# uC.net
KiCad netlist of a schematic drawn in Altium Designer
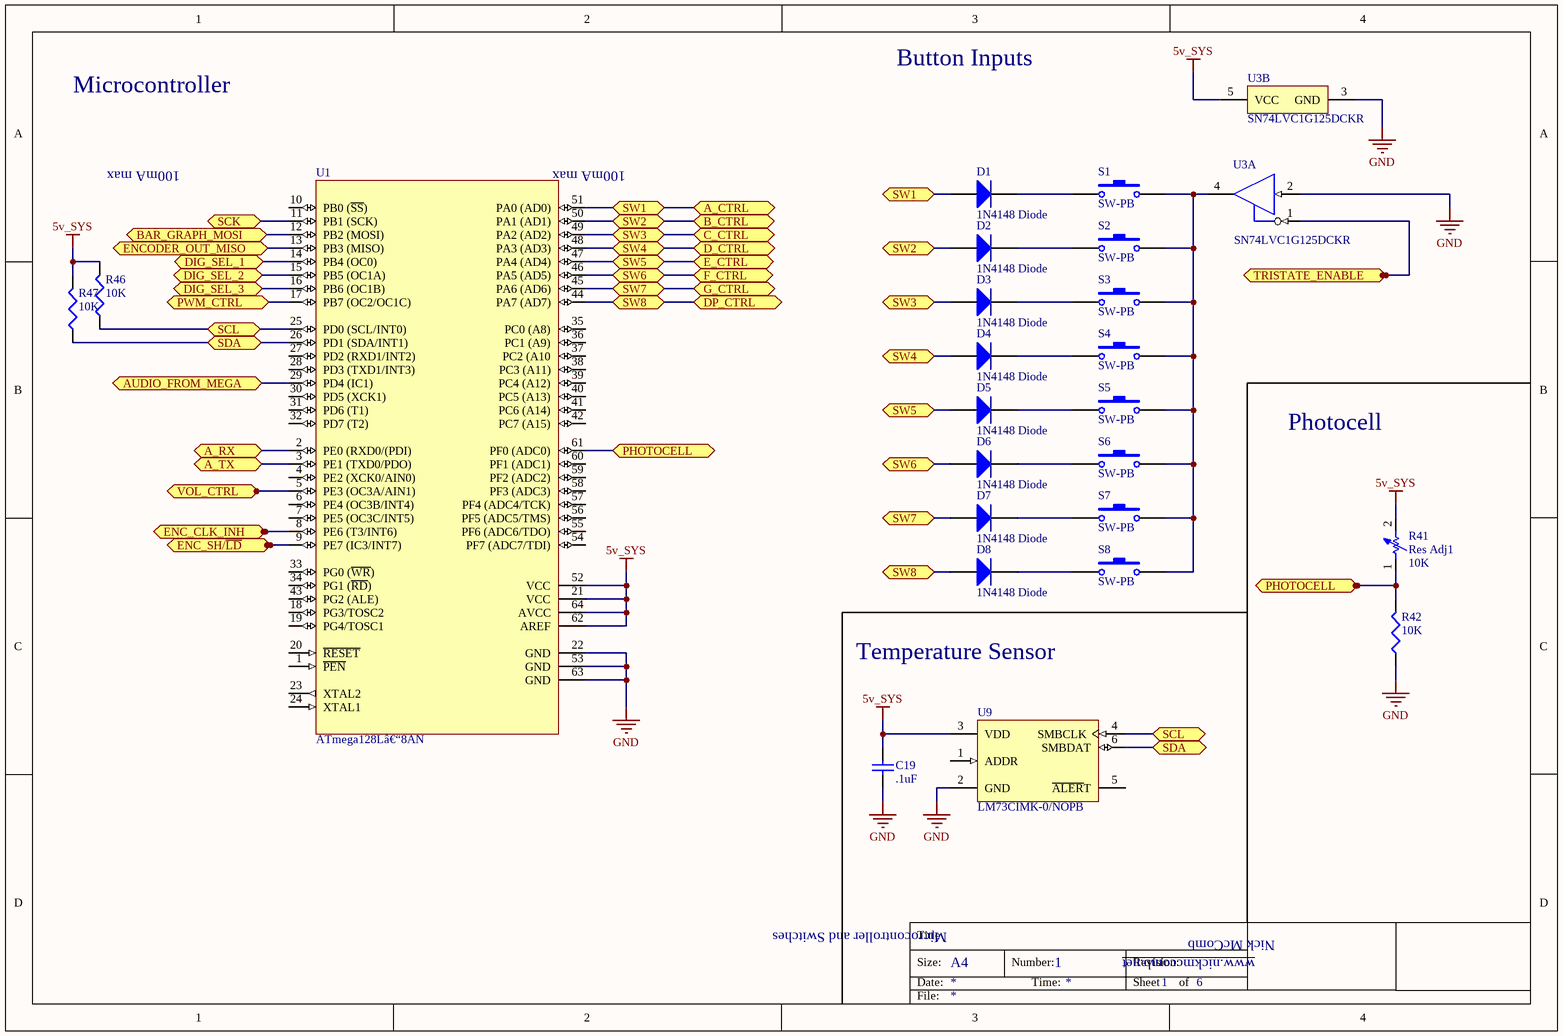
[diagram p0: uC.SchDoc]

(export (version "E")
  (design (tool "Eeschema 10.0.6"))
  (components
    (comp (ref "C19")
      (value ".1uF")
      (footprint "C0805")
      (description "Capacitor")
      (fields (field (name "Comment") "0805 style, by default") (field (name "PUBLISHER") "Altium Limited"))
      (libsource (lib "mega48") (part "Cap"))
    )
    (comp (ref "D1")
      (value "1N4148 Diode")
      (footprint "S01575 Diode")
      (description "Diode")
      (libsource (lib "lab2") (part "Diode"))
    )
    (comp (ref "D2")
      (value "1N4148 Diode")
      (footprint "S01575 Diode")
      (description "Diode")
      (libsource (lib "lab2") (part "Diode"))
    )
    (comp (ref "D3")
      (value "1N4148 Diode")
      (footprint "S01575 Diode")
      (description "Diode")
      (libsource (lib "lab2") (part "Diode"))
    )
    (comp (ref "D4")
      (value "1N4148 Diode")
      (footprint "S01575 Diode")
      (description "Diode")
      (libsource (lib "lab2") (part "Diode"))
    )
    (comp (ref "D5")
      (value "1N4148 Diode")
      (footprint "S01575 Diode")
      (description "Diode")
      (libsource (lib "lab2") (part "Diode"))
    )
    (comp (ref "D6")
      (value "1N4148 Diode")
      (footprint "S01575 Diode")
      (description "Diode")
      (libsource (lib "lab2") (part "Diode"))
    )
    (comp (ref "D7")
      (value "1N4148 Diode")
      (footprint "S01575 Diode")
      (description "Diode")
      (libsource (lib "lab2") (part "Diode"))
    )
    (comp (ref "D8")
      (value "1N4148 Diode")
      (footprint "S01575 Diode")
      (description "Diode")
      (libsource (lib "lab2") (part "Diode"))
    )
    (comp (ref "R41")
      (value "Res Adj1")
      (footprint "LOG POT")
      (description "Variable Resistor")
      (fields (field (name "ALTIUM_VALUE") "10K"))
      (libsource (lib "lab2") (part "Res Adj1"))
    )
    (comp (ref "R42")
      (value "10K")
      (footprint "J1-0603")
      (description "Resistor")
      (fields (field (name "PUBLISHER") "Altium Limited"))
      (libsource (lib "lab2") (part "Res3"))
    )
    (comp (ref "R46")
      (value "10K")
      (footprint "J1-0603")
      (description "Resistor")
      (fields (field (name "PUBLISHER") "Altium Limited"))
      (libsource (lib "lab2") (part "Res3"))
    )
    (comp (ref "R47")
      (value "10K")
      (footprint "J1-0603")
      (description "Resistor")
      (fields (field (name "PUBLISHER") "Altium Limited"))
      (libsource (lib "lab2") (part "Res3"))
    )
    (comp (ref "S1")
      (value "SW-PB")
      (footprint "SW-PB")
      (description "Switch")
      (libsource (lib "lab2") (part "SW-PB"))
    )
    (comp (ref "S2")
      (value "SW-PB")
      (footprint "SW-PB")
      (description "Switch")
      (libsource (lib "lab2") (part "SW-PB"))
    )
    (comp (ref "S3")
      (value "SW-PB")
      (footprint "SW-PB")
      (description "Switch")
      (libsource (lib "lab2") (part "SW-PB"))
    )
    (comp (ref "S4")
      (value "SW-PB")
      (footprint "SW-PB")
      (description "Switch")
      (libsource (lib "lab2") (part "SW-PB"))
    )
    (comp (ref "S5")
      (value "SW-PB")
      (footprint "SW-PB")
      (description "Switch")
      (libsource (lib "lab2") (part "SW-PB"))
    )
    (comp (ref "S6")
      (value "SW-PB")
      (footprint "SW-PB")
      (description "Switch")
      (libsource (lib "lab2") (part "SW-PB"))
    )
    (comp (ref "S7")
      (value "SW-PB")
      (footprint "SW-PB")
      (description "Switch")
      (libsource (lib "lab2") (part "SW-PB"))
    )
    (comp (ref "S8")
      (value "SW-PB")
      (footprint "SW-PB")
      (description "Switch")
      (libsource (lib "lab2") (part "SW-PB"))
    )
    (comp (ref "U1")
      (value "ATmega128Lâ€“8AN")
      (footprint "64A_M")
      (libsource (lib "Altium Content Vault") (part "MC-8B-AT64-SQ64"))
    )
    (comp (ref "U3")
      (value "SN74LVC1G125DCKR")
      (footprint "DCK0005A_M")
      (description "Single Bus Buffer Gate With 3-State Outputs, DCK0005A, LARGE T&R")
      (fields
        (field (name "GENERIC PART NUMBER") "SN74LVC1G125")
        (field (name "MANUFACTURER") "Texas Instruments")
      )
      (libsource (lib "Altium Content Vault") (part "TI-SN74AXXXX1X125-5"))
    )
    (comp (ref "U9")
      (value "LM73CIMK-0/NOPB")
      (footprint "DDC0006A_M")
      (description "2.7V, 11- to 14- Bit Digital Temperature Sensor with 2-Wire Interface, 6-pin Tiny SOT23, Pb-Free")
      (fields (field (name "MANUFACTURER") "Texas Instruments"))
      (libsource (lib "Altium Content Vault") (part "SEN-TEMP-LM73CIMK-6"))
    )
  )
  (nets
    (net (code "1") (name "/AUDIO_FROM_MEGA") (class "Default")
      (node (ref "U1") (pin "29") (pinfunction "PD4_(IC1)_29") (pintype "bidirectional"))
    )
    (net (code "2") (name "/A_CTRL") (class "Default")
      (node (ref "D1") (pin "3") (pinfunction "A_3") (pintype "passive"))
      (node (ref "U1") (pin "51") (pinfunction "PA0_(AD0)_51") (pintype "bidirectional"))
    )
    (net (code "3") (name "/A_RX") (class "Default")
      (node (ref "U1") (pin "2") (pinfunction "PE0_(RXD0/(PDI)_2") (pintype "bidirectional"))
    )
    (net (code "4") (name "/A_TX") (class "Default")
      (node (ref "U1") (pin "3") (pinfunction "PE1_(TXD0/PDO)_3") (pintype "bidirectional"))
    )
    (net (code "5") (name "/BAR_GRAPH_MOSI") (class "Default")
      (node (ref "U1") (pin "12") (pinfunction "PB2_(MOSI)_12") (pintype "bidirectional"))
    )
    (net (code "6") (name "/B_CTRL") (class "Default")
      (node (ref "D2") (pin "3") (pinfunction "A_3") (pintype "passive"))
      (node (ref "U1") (pin "50") (pinfunction "PA1_(AD1)_50") (pintype "bidirectional"))
    )
    (net (code "7") (name "/C_CTRL") (class "Default")
      (node (ref "D3") (pin "3") (pinfunction "A_3") (pintype "passive"))
      (node (ref "U1") (pin "49") (pinfunction "PA2_(AD2)_49") (pintype "bidirectional"))
    )
    (net (code "8") (name "/DIG_SEL_1") (class "Default")
      (node (ref "U1") (pin "14") (pinfunction "PB4_(OC0)_14") (pintype "bidirectional"))
    )
    (net (code "9") (name "/DIG_SEL_2") (class "Default")
      (node (ref "U1") (pin "15") (pinfunction "PB5_(OC1A)_15") (pintype "bidirectional"))
    )
    (net (code "10") (name "/DIG_SEL_3") (class "Default")
      (node (ref "U1") (pin "16") (pinfunction "PB6_(OC1B)_16") (pintype "bidirectional"))
    )
    (net (code "11") (name "/DP_CTRL") (class "Default")
      (node (ref "D8") (pin "3") (pinfunction "A_3") (pintype "passive"))
      (node (ref "U1") (pin "44") (pinfunction "PA7_(AD7)_44") (pintype "bidirectional"))
    )
    (net (code "12") (name "/D_CTRL") (class "Default")
      (node (ref "D4") (pin "3") (pinfunction "A_3") (pintype "passive"))
      (node (ref "U1") (pin "48") (pinfunction "PA3_(AD3)_48") (pintype "bidirectional"))
    )
    (net (code "13") (name "/ENCODER_OUT_MISO") (class "Default")
      (node (ref "U1") (pin "13") (pinfunction "PB3_(MISO)_13") (pintype "bidirectional"))
    )
    (net (code "14") (name "/ENC_CLK_INH") (class "Default")
      (node (ref "U1") (pin "8") (pinfunction "PE6_(T3/INT6)_8") (pintype "bidirectional"))
    )
    (net (code "15") (name "/ENC_SH{slash}~{LD}") (class "Default")
      (node (ref "U1") (pin "9") (pinfunction "PE7_(IC3/INT7)_9") (pintype "bidirectional"))
    )
    (net (code "16") (name "/E_CTRL") (class "Default")
      (node (ref "D5") (pin "3") (pinfunction "A_3") (pintype "passive"))
      (node (ref "U1") (pin "47") (pinfunction "PA4_(AD4)_47") (pintype "bidirectional"))
    )
    (net (code "17") (name "/F_CTRL") (class "Default")
      (node (ref "D6") (pin "3") (pinfunction "A_3") (pintype "passive"))
      (node (ref "U1") (pin "46") (pinfunction "PA5_(AD5)_46") (pintype "bidirectional"))
    )
    (net (code "18") (name "/G_CTRL") (class "Default")
      (node (ref "D7") (pin "3") (pinfunction "A_3") (pintype "passive"))
      (node (ref "U1") (pin "45") (pinfunction "PA6_(AD6)_45") (pintype "bidirectional"))
    )
    (net (code "19") (name "/PHOTOCELL") (class "Default")
      (node (ref "R41") (pin "1") (pinfunction "1_1") (pintype "passive"))
      (node (ref "R42") (pin "2") (pinfunction "2_2") (pintype "passive"))
      (node (ref "U1") (pin "61") (pinfunction "PF0_(ADC0)_61") (pintype "bidirectional"))
    )
    (net (code "20") (name "/PWM_CTRL") (class "Default")
      (node (ref "U1") (pin "17") (pinfunction "PB7_(OC2/OC1C)_17") (pintype "bidirectional"))
    )
    (net (code "21") (name "/SCK") (class "Default")
      (node (ref "U1") (pin "11") (pinfunction "PB1_(SCK)_11") (pintype "bidirectional"))
    )
    (net (code "22") (name "/SCL") (class "Default")
      (node (ref "R46") (pin "1") (pinfunction "1_1") (pintype "passive"))
      (node (ref "U1") (pin "25") (pinfunction "PD0_(SCL/INT0)_25") (pintype "bidirectional"))
      (node (ref "U9") (pin "4") (pinfunction "SMBCLK_4") (pintype "input"))
    )
    (net (code "23") (name "/SDA") (class "Default")
      (node (ref "R47") (pin "1") (pinfunction "1_1") (pintype "passive"))
      (node (ref "U1") (pin "26") (pinfunction "PD1_(SDA/INT1)_26") (pintype "bidirectional"))
      (node (ref "U9") (pin "6") (pinfunction "SMBDAT_6") (pintype "bidirectional"))
    )
    (net (code "24") (name "/TRISTATE_ENABLE") (class "Default")
      (node (ref "U3") (pin "1") (pinfunction "~{OE}_1") (pintype "input"))
    )
    (net (code "25") (name "/VOL_CTRL") (class "Default")
      (node (ref "U1") (pin "5") (pinfunction "PE3_(OC3A/AIN1)_5") (pintype "bidirectional"))
    )
    (net (code "26") (name "5v_SYS") (class "Default")
      (node (ref "C19") (pin "2") (pinfunction "2_2") (pintype "passive"))
      (node (ref "R41") (pin "2") (pinfunction "2_2") (pintype "passive"))
      (node (ref "R46") (pin "2") (pinfunction "2_2") (pintype "passive"))
      (node (ref "R47") (pin "2") (pinfunction "2_2") (pintype "passive"))
      (node (ref "U1") (pin "21") (pinfunction "VCC_21") (pintype "power_in"))
      (node (ref "U1") (pin "52") (pinfunction "VCC_52") (pintype "power_in"))
      (node (ref "U1") (pin "62") (pinfunction "AREF_62") (pintype "passive"))
      (node (ref "U1") (pin "64") (pinfunction "AVCC_64") (pintype "power_in"))
      (node (ref "U3") (pin "5") (pinfunction "VCC_5") (pintype "power_in"))
      (node (ref "U9") (pin "3") (pinfunction "VDD_3") (pintype "power_in"))
    )
    (net (code "27") (name "GND") (class "Default")
      (node (ref "C19") (pin "1") (pinfunction "1_1") (pintype "passive"))
      (node (ref "R42") (pin "1") (pinfunction "1_1") (pintype "passive"))
      (node (ref "U1") (pin "22") (pinfunction "GND_22") (pintype "power_in"))
      (node (ref "U1") (pin "53") (pinfunction "GND_53") (pintype "power_in"))
      (node (ref "U1") (pin "63") (pinfunction "GND_63") (pintype "power_in"))
      (node (ref "U3") (pin "2") (pinfunction "A_2") (pintype "input"))
      (node (ref "U3") (pin "3") (pinfunction "GND_3") (pintype "power_in"))
      (node (ref "U9") (pin "2") (pinfunction "GND_2") (pintype "power_in"))
    )
    (net (code "28") (name "Net-(D1-K)") (class "Default")
      (node (ref "D1") (pin "1") (pinfunction "K_1") (pintype "passive"))
      (node (ref "S1") (pin "1") (pinfunction "1_1") (pintype "passive"))
    )
    (net (code "29") (name "Net-(D2-K)") (class "Default")
      (node (ref "D2") (pin "1") (pinfunction "K_1") (pintype "passive"))
      (node (ref "S2") (pin "1") (pinfunction "1_1") (pintype "passive"))
    )
    (net (code "30") (name "Net-(D3-K)") (class "Default")
      (node (ref "D3") (pin "1") (pinfunction "K_1") (pintype "passive"))
      (node (ref "S3") (pin "1") (pinfunction "1_1") (pintype "passive"))
    )
    (net (code "31") (name "Net-(D4-K)") (class "Default")
      (node (ref "D4") (pin "1") (pinfunction "K_1") (pintype "passive"))
      (node (ref "S4") (pin "1") (pinfunction "1_1") (pintype "passive"))
    )
    (net (code "32") (name "Net-(D5-K)") (class "Default")
      (node (ref "D5") (pin "1") (pinfunction "K_1") (pintype "passive"))
      (node (ref "S5") (pin "1") (pinfunction "1_1") (pintype "passive"))
    )
    (net (code "33") (name "Net-(D6-K)") (class "Default")
      (node (ref "D6") (pin "1") (pinfunction "K_1") (pintype "passive"))
      (node (ref "S6") (pin "1") (pinfunction "1_1") (pintype "passive"))
    )
    (net (code "34") (name "Net-(D7-K)") (class "Default")
      (node (ref "D7") (pin "1") (pinfunction "K_1") (pintype "passive"))
      (node (ref "S7") (pin "1") (pinfunction "1_1") (pintype "passive"))
    )
    (net (code "35") (name "Net-(D8-K)") (class "Default")
      (node (ref "D8") (pin "1") (pinfunction "K_1") (pintype "passive"))
      (node (ref "S8") (pin "1") (pinfunction "1_1") (pintype "passive"))
    )
    (net (code "36") (name "Net-(U3A-Y)") (class "Default")
      (node (ref "S1") (pin "2") (pinfunction "2_2") (pintype "passive"))
      (node (ref "S2") (pin "2") (pinfunction "2_2") (pintype "passive"))
      (node (ref "S3") (pin "2") (pinfunction "2_2") (pintype "passive"))
      (node (ref "S4") (pin "2") (pinfunction "2_2") (pintype "passive"))
      (node (ref "S5") (pin "2") (pinfunction "2_2") (pintype "passive"))
      (node (ref "S6") (pin "2") (pinfunction "2_2") (pintype "passive"))
      (node (ref "S7") (pin "2") (pinfunction "2_2") (pintype "passive"))
      (node (ref "S8") (pin "2") (pinfunction "2_2") (pintype "passive"))
      (node (ref "U3") (pin "4") (pinfunction "Y_4") (pintype "tri_state"))
    )
    (net (code "37") (name "unconnected-(U1-PB0_(~{SS})-Pad10)") (class "Default")
      (node (ref "U1") (pin "10") (pinfunction "PB0_(~{SS})_10") (pintype "bidirectional"))
    )
    (net (code "38") (name "unconnected-(U1-PC0_(A8)-Pad35)") (class "Default")
      (node (ref "U1") (pin "35") (pinfunction "PC0_(A8)_35") (pintype "bidirectional"))
    )
    (net (code "39") (name "unconnected-(U1-PC1_(A9)-Pad36)") (class "Default")
      (node (ref "U1") (pin "36") (pinfunction "PC1_(A9)_36") (pintype "bidirectional"))
    )
    (net (code "40") (name "unconnected-(U1-PC2_(A10-Pad37)") (class "Default")
      (node (ref "U1") (pin "37") (pinfunction "PC2_(A10_37") (pintype "bidirectional"))
    )
    (net (code "41") (name "unconnected-(U1-PC3_(A11)-Pad38)") (class "Default")
      (node (ref "U1") (pin "38") (pinfunction "PC3_(A11)_38") (pintype "bidirectional"))
    )
    (net (code "42") (name "unconnected-(U1-PC4_(A12)-Pad39)") (class "Default")
      (node (ref "U1") (pin "39") (pinfunction "PC4_(A12)_39") (pintype "bidirectional"))
    )
    (net (code "43") (name "unconnected-(U1-PC5_(A13)-Pad40)") (class "Default")
      (node (ref "U1") (pin "40") (pinfunction "PC5_(A13)_40") (pintype "bidirectional"))
    )
    (net (code "44") (name "unconnected-(U1-PC6_(A14)-Pad41)") (class "Default")
      (node (ref "U1") (pin "41") (pinfunction "PC6_(A14)_41") (pintype "bidirectional"))
    )
    (net (code "45") (name "unconnected-(U1-PC7_(A15)-Pad42)") (class "Default")
      (node (ref "U1") (pin "42") (pinfunction "PC7_(A15)_42") (pintype "bidirectional"))
    )
    (net (code "46") (name "unconnected-(U1-PD2_(RXD1{slash}INT2)-Pad27)") (class "Default")
      (node (ref "U1") (pin "27") (pinfunction "PD2_(RXD1/INT2)_27") (pintype "bidirectional"))
    )
    (net (code "47") (name "unconnected-(U1-PD3_(TXD1{slash}INT3)-Pad28)") (class "Default")
      (node (ref "U1") (pin "28") (pinfunction "PD3_(TXD1/INT3)_28") (pintype "bidirectional"))
    )
    (net (code "48") (name "unconnected-(U1-PD5_(XCK1)-Pad30)") (class "Default")
      (node (ref "U1") (pin "30") (pinfunction "PD5_(XCK1)_30") (pintype "bidirectional"))
    )
    (net (code "49") (name "unconnected-(U1-PD6_(T1)-Pad31)") (class "Default")
      (node (ref "U1") (pin "31") (pinfunction "PD6_(T1)_31") (pintype "bidirectional"))
    )
    (net (code "50") (name "unconnected-(U1-PD7_(T2)-Pad32)") (class "Default")
      (node (ref "U1") (pin "32") (pinfunction "PD7_(T2)_32") (pintype "bidirectional"))
    )
    (net (code "51") (name "unconnected-(U1-PE2_(XCK0{slash}AIN0)-Pad4)") (class "Default")
      (node (ref "U1") (pin "4") (pinfunction "PE2_(XCK0/AIN0)_4") (pintype "bidirectional"))
    )
    (net (code "52") (name "unconnected-(U1-PE4_(OC3B{slash}INT4)-Pad6)") (class "Default")
      (node (ref "U1") (pin "6") (pinfunction "PE4_(OC3B/INT4)_6") (pintype "bidirectional"))
    )
    (net (code "53") (name "unconnected-(U1-PE5_(OC3C{slash}INT5)-Pad7)") (class "Default")
      (node (ref "U1") (pin "7") (pinfunction "PE5_(OC3C/INT5)_7") (pintype "bidirectional"))
    )
    (net (code "54") (name "unconnected-(U1-PF1_(ADC1)-Pad60)") (class "Default")
      (node (ref "U1") (pin "60") (pinfunction "PF1_(ADC1)_60") (pintype "bidirectional"))
    )
    (net (code "55") (name "unconnected-(U1-PF2_(ADC2)-Pad59)") (class "Default")
      (node (ref "U1") (pin "59") (pinfunction "PF2_(ADC2)_59") (pintype "bidirectional"))
    )
    (net (code "56") (name "unconnected-(U1-PF3_(ADC3)-Pad58)") (class "Default")
      (node (ref "U1") (pin "58") (pinfunction "PF3_(ADC3)_58") (pintype "bidirectional"))
    )
    (net (code "57") (name "unconnected-(U1-PF4_(ADC4{slash}TCK)-Pad57)") (class "Default")
      (node (ref "U1") (pin "57") (pinfunction "PF4_(ADC4/TCK)_57") (pintype "bidirectional"))
    )
    (net (code "58") (name "unconnected-(U1-PF5_(ADC5{slash}TMS)-Pad56)") (class "Default")
      (node (ref "U1") (pin "56") (pinfunction "PF5_(ADC5/TMS)_56") (pintype "bidirectional"))
    )
    (net (code "59") (name "unconnected-(U1-PF6_(ADC6{slash}TDO)-Pad55)") (class "Default")
      (node (ref "U1") (pin "55") (pinfunction "PF6_(ADC6/TDO)_55") (pintype "bidirectional"))
    )
    (net (code "60") (name "unconnected-(U1-PF7_(ADC7{slash}TDI)-Pad54)") (class "Default")
      (node (ref "U1") (pin "54") (pinfunction "PF7_(ADC7/TDI)_54") (pintype "bidirectional"))
    )
    (net (code "61") (name "unconnected-(U1-PG0_(~{WR})-Pad33)") (class "Default")
      (node (ref "U1") (pin "33") (pinfunction "PG0_(~{WR})_33") (pintype "bidirectional"))
    )
    (net (code "62") (name "unconnected-(U1-PG1_(~{RD})-Pad34)") (class "Default")
      (node (ref "U1") (pin "34") (pinfunction "PG1_(~{RD})_34") (pintype "bidirectional"))
    )
    (net (code "63") (name "unconnected-(U1-PG2_(ALE)-Pad43)") (class "Default")
      (node (ref "U1") (pin "43") (pinfunction "PG2_(ALE)_43") (pintype "bidirectional"))
    )
    (net (code "64") (name "unconnected-(U1-PG3{slash}TOSC2-Pad18)") (class "Default")
      (node (ref "U1") (pin "18") (pinfunction "PG3/TOSC2_18") (pintype "bidirectional"))
    )
    (net (code "65") (name "unconnected-(U1-PG4{slash}TOSC1-Pad19)") (class "Default")
      (node (ref "U1") (pin "19") (pinfunction "PG4/TOSC1_19") (pintype "bidirectional"))
    )
    (net (code "66") (name "unconnected-(U1-XTAL1-Pad24)") (class "Default")
      (node (ref "U1") (pin "24") (pinfunction "XTAL1_24") (pintype "input"))
    )
    (net (code "67") (name "unconnected-(U1-XTAL2-Pad23)") (class "Default")
      (node (ref "U1") (pin "23") (pinfunction "XTAL2_23") (pintype "output"))
    )
    (net (code "68") (name "unconnected-(U1-~{PEN}-Pad1)") (class "Default")
      (node (ref "U1") (pin "1") (pinfunction "~{PEN}_1") (pintype "input"))
    )
    (net (code "69") (name "unconnected-(U1-~{RESET}-Pad20)") (class "Default")
      (node (ref "U1") (pin "20") (pinfunction "~{RESET}_20") (pintype "input"))
    )
    (net (code "70") (name "unconnected-(U9-ADDR-Pad1)") (class "Default")
      (node (ref "U9") (pin "1") (pinfunction "ADDR_1") (pintype "input"))
    )
    (net (code "71") (name "unconnected-(U9-~{ALER}T-Pad5)") (class "Default")
      (node (ref "U9") (pin "5") (pinfunction "~{ALER}T_5") (pintype "open_collector"))
    )
  )
)
